# measurement_ch1.net
KiCad netlist of a schematic drawn in Altium Designer
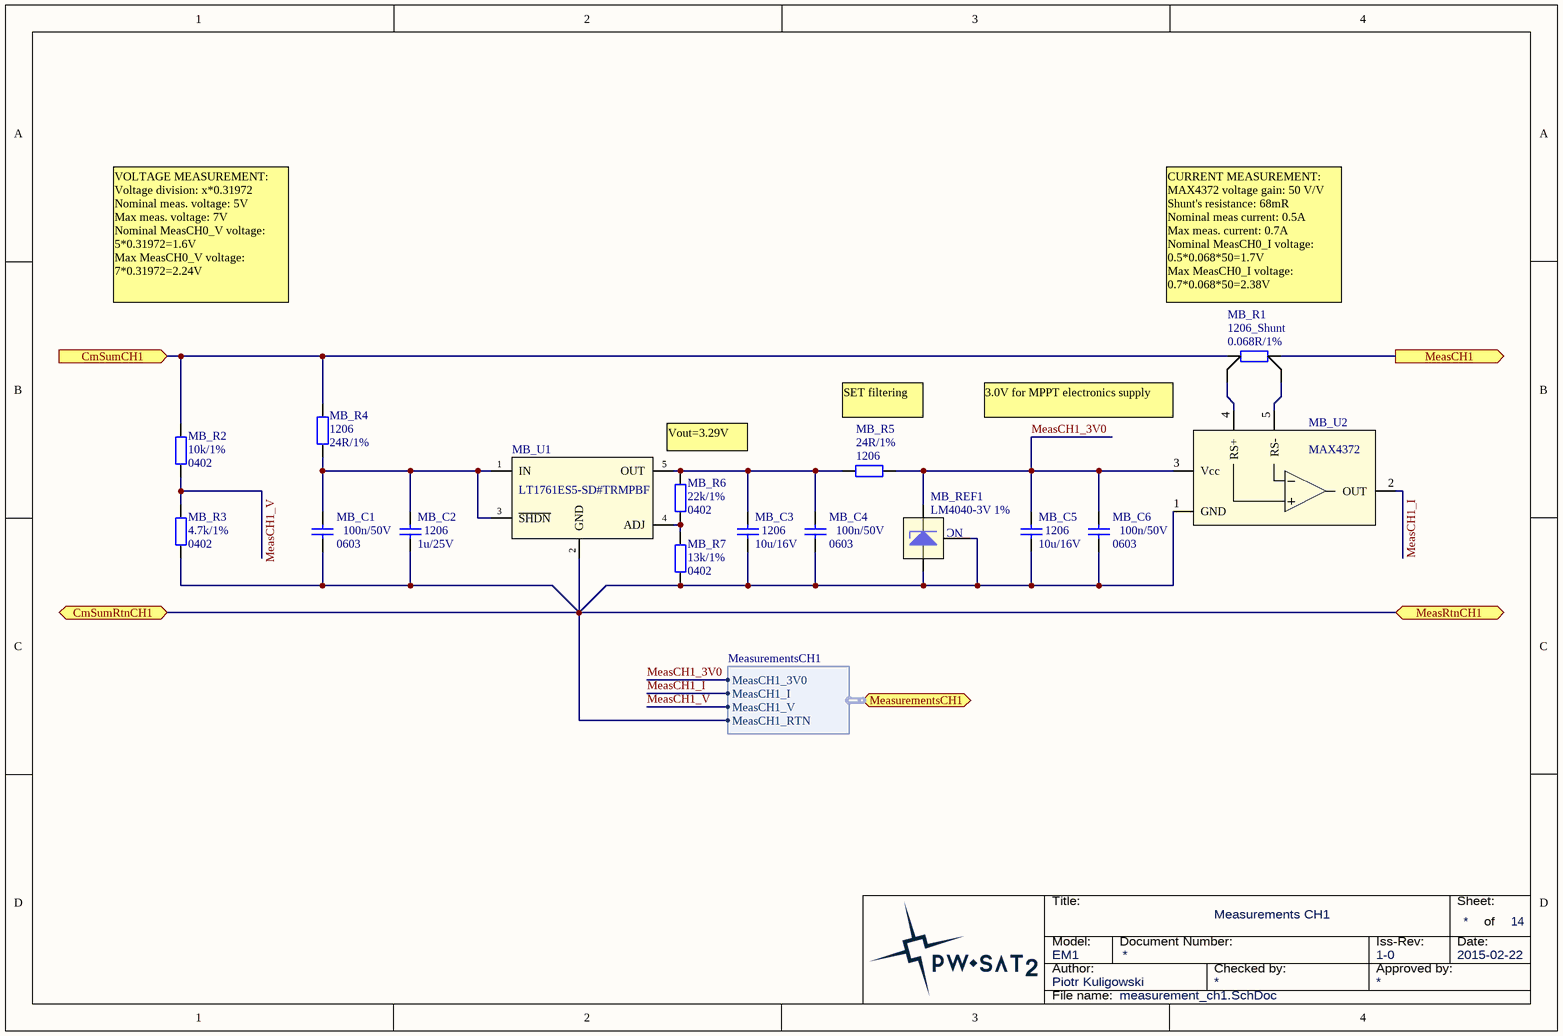
[diagram p0: measurement_ch1.SchDoc]

(export (version "E")
  (design (tool "Eeschema 10.0.6"))
  (components
    (comp (ref "MB_C1")
      (value "100n/50V")
      (footprint "SMD_Capacitor_0603")
      (description "Ceramic Cap Murata Automotive 100n/50V X7R 0603")
      (fields
        (field (name "MANUFACTURER") "Murata")
        (field (name "MANUFACTURERPARTNUMBER") "GCJ188R71H104KA12D")
        (field (name "PACKAGE") "0603")
      )
      (libsource (lib "capacitors") (part "Cer_GCJ188R71H104KA12D"))
    )
    (comp (ref "MB_C2")
      (value "1u/25V")
      (footprint "SMD_Capacitor_1206")
      (description "Ceramic Cap Kemet COTS 1u/25V X7R 1206")
      (fields
        (field (name "MANUFACTURERPARTNUMBER") "C1206T105K3RALTU")
        (field (name "MANUFACTURER") "Kemet")
        (field (name "PACKAGE") "1206")
      )
      (libsource (lib "capacitors") (part "Cer_C1206T105K3RALTU"))
    )
    (comp (ref "MB_C3")
      (value "10u/16V")
      (footprint "SMD_Capacitor_1206")
      (description "Ceramic Cap Kemet COTS 10u/16V X7R 1206")
      (fields
        (field (name "MANUFACTURERPARTNUMBER") "C1206T106K4RACTU")
        (field (name "MANUFACTURER") "Kemet")
        (field (name "PACKGE") "1206")
      )
      (libsource (lib "capacitors") (part "Cer_C1206T106K4RACTU"))
    )
    (comp (ref "MB_C4")
      (value "100n/50V")
      (footprint "SMD_Capacitor_0603")
      (description "Ceramic Cap Murata Automotive 100n/50V X7R 0603")
      (fields
        (field (name "MANUFACTURER") "Murata")
        (field (name "MANUFACTURERPARTNUMBER") "GCJ188R71H104KA12D")
        (field (name "PACKAGE") "0603")
      )
      (libsource (lib "capacitors") (part "Cer_GCJ188R71H104KA12D"))
    )
    (comp (ref "MB_C5")
      (value "10u/16V")
      (footprint "SMD_Capacitor_1206")
      (description "Ceramic Cap Kemet COTS 10u/16V X7R 1206")
      (fields
        (field (name "MANUFACTURERPARTNUMBER") "C1206T106K4RACTU")
        (field (name "MANUFACTURER") "Kemet")
        (field (name "PACKGE") "1206")
      )
      (libsource (lib "capacitors") (part "Cer_C1206T106K4RACTU"))
    )
    (comp (ref "MB_C6")
      (value "100n/50V")
      (footprint "SMD_Capacitor_0603")
      (description "Ceramic Cap Murata Automotive 100n/50V X7R 0603")
      (fields
        (field (name "MANUFACTURER") "Murata")
        (field (name "MANUFACTURERPARTNUMBER") "GCJ188R71H104KA12D")
        (field (name "PACKAGE") "0603")
      )
      (libsource (lib "capacitors") (part "Cer_GCJ188R71H104KA12D"))
    )
    (comp (ref "MB_R1")
      (value "0.068R/1%")
      (footprint "SMD_Resistor-Shunt_1206")
      (description "Panasonic Resistor 68mR 1% 1206 1W")
      (fields
        (field (name "MANUFACTURER") "Panasonic")
        (field (name "MANUFACTURERPARTNUMBER") "ERJ-8BWFR068V")
        (field (name "PACKAGE") "1206_Shunt")
      )
      (libsource (lib "resistors") (part "ERJ-8BWFR068V"))
    )
    (comp (ref "MB_R2")
      (value "10k/1%")
      (footprint "SMD_Resistor_0402")
      (description "10k/1% Vishay CRCW 0402 Resistor. 63mW, 100ppm, 50V.")
      (fields
        (field (name "MANUFACTURER") "Vishay")
        (field (name "MANUFACTURERPARTNUMBER") "CRCW040210K0FKxxxx")
        (field (name "PACKAGE") "0402")
      )
      (libsource (lib "resistors") (part "CRCW040210K0FKxxxx"))
    )
    (comp (ref "MB_R3")
      (value "4.7k/1%")
      (footprint "SMD_Resistor_0402")
      (description "4.7k/1% Vishay CRCW 0402 Resistor. 63mW, 100ppm, 50V.")
      (fields
        (field (name "MANUFACTURERPARTNUMBER") "CRCW04024K70FKxxxx")
        (field (name "MANUFACTURER") "Vishay")
        (field (name "PACKAGE") "0402")
      )
      (libsource (lib "resistors") (part "CRCW04024K70FKxxxx"))
    )
    (comp (ref "MB_R4")
      (value "24R/1%")
      (footprint "SMD_Resistor_1206")
      (description "24R/1% Vishay CRCW 1206 Resistor. 250mW, 100ppm, 200V.")
      (fields
        (field (name "MANUFACTURERPARTNUMBER") "CRCW120624R0FKxxxx")
        (field (name "MANUFACTURER") "Vishay")
        (field (name "PACKAGE") "1206")
      )
      (libsource (lib "resistors") (part "CRCW120624R0FKxxxx"))
    )
    (comp (ref "MB_R5")
      (value "24R/1%")
      (footprint "SMD_Resistor_1206")
      (description "24R/1% Vishay CRCW 1206 Resistor. 250mW, 100ppm, 200V.")
      (fields
        (field (name "MANUFACTURERPARTNUMBER") "CRCW120624R0FKxxxx")
        (field (name "MANUFACTURER") "Vishay")
        (field (name "PACKAGE") "1206")
      )
      (libsource (lib "") (part "CRCW120624R0FKxxxx_1"))
    )
    (comp (ref "MB_R6")
      (value "22k/1%")
      (footprint "SMD_Resistor_0402")
      (description "22k/1% Vishay CRCW 0402 Resistor. 63mW, 100ppm, 50V.")
      (fields
        (field (name "MANUFACTURER") "Vishay")
        (field (name "MANUFACTURERPARTNUMBER") "CRCW040222K0FKxxxx")
        (field (name "PACKAGE") "0402")
      )
      (libsource (lib "resistors") (part "CRCW040222K0FKxxxx"))
    )
    (comp (ref "MB_R7")
      (value "13k/1%")
      (footprint "SMD_Resistor_0402")
      (description "13k/1% Vishay CRCW 0402 Resistor. 63mW, 100ppm, 50V.")
      (fields
        (field (name "MANUFACTURERPARTNUMBER") "CRCW040213K0FKxxxx")
        (field (name "MANUFACTURER") "Vishay")
        (field (name "PACKAGE") "0402")
      )
      (libsource (lib "resistors") (part "CRCW040213K0FKxxxx"))
    )
    (comp (ref "MB_REF1")
      (value "LM4040-3V 1%")
      (footprint "SOT23-3")
      (description "Shunt V-REF, 3V, 1%, SOT23-3")
      (fields
        (field (name "MANUFACTURERPARTNUMBER") "LM4040DIM3-3.0")
        (field (name "MANUFACTURER") "Texas Instruments")
      )
      (libsource (lib "diodes") (part "LM4040DIM3-3.0"))
    )
    (comp (ref "MB_U1")
      (value "LT1761ES5-SD#TRMPBF")
      (footprint "SOT23-5")
      (description "100mA, Regulated, Low Noise, LDO Micropower Regulator in TSOT-23")
      (fields (field (name "MANUFACTURER") "Linear Technology"))
      (libsource (lib "microcircuits") (part "LT1761ES5-SD#TRMPBF"))
    )
    (comp (ref "MB_U2")
      (value "MAX4372")
      (footprint "SOT23-5")
      (description "High-Side Current-Sense Amplifier with Voltage Output")
      (fields (field (name "MANUFACTURER") "Maxim Integrated Products"))
      (libsource (lib "microcircuits") (part "MAX4372"))
    )
  )
  (nets
    (net (code "2") (name "/CmSumCH1") (class "Default")
      (node (ref "MB_R1") (pin "1") (pinfunction "1_1") (pintype "passive"))
      (node (ref "MB_R2") (pin "1") (pinfunction "1_1") (pintype "passive"))
      (node (ref "MB_R4") (pin "1") (pinfunction "1_1") (pintype "passive"))
    )
    (net (code "3") (name "/CmSumRtnCH1") (class "Default")
      (node (ref "MB_C1") (pin "2") (pinfunction "2_2") (pintype "passive"))
      (node (ref "MB_C2") (pin "2") (pinfunction "2_2") (pintype "passive"))
      (node (ref "MB_C3") (pin "2") (pinfunction "2_2") (pintype "passive"))
      (node (ref "MB_C4") (pin "2") (pinfunction "2_2") (pintype "passive"))
      (node (ref "MB_C5") (pin "2") (pinfunction "2_2") (pintype "passive"))
      (node (ref "MB_C6") (pin "2") (pinfunction "2_2") (pintype "passive"))
      (node (ref "MB_R3") (pin "2") (pinfunction "2_2") (pintype "passive"))
      (node (ref "MB_R7") (pin "2") (pinfunction "2_2") (pintype "passive"))
      (node (ref "MB_REF1") (pin "2") (pinfunction "A_2") (pintype "passive"))
      (node (ref "MB_REF1") (pin "3") (pinfunction "NC_3") (pintype "passive"))
      (node (ref "MB_U1") (pin "2") (pinfunction "GND_2") (pintype "passive"))
      (node (ref "MB_U2") (pin "1") (pinfunction "GND_1") (pintype "passive"))
    )
    (net (code "4") (name "/MeasCH1") (class "Default")
      (node (ref "MB_R1") (pin "4") (pinfunction "4_4") (pintype "passive"))
    )
    (net (code "5") (name "/MeasCH1_3V0") (class "Default")
      (node (ref "MB_C5") (pin "1") (pinfunction "1_1") (pintype "passive"))
      (node (ref "MB_C6") (pin "1") (pinfunction "1_1") (pintype "passive"))
      (node (ref "MB_R5") (pin "2") (pinfunction "2_2") (pintype "passive"))
      (node (ref "MB_REF1") (pin "1") (pinfunction "K_1") (pintype "passive"))
      (node (ref "MB_U2") (pin "3") (pinfunction "Vcc_3") (pintype "passive"))
    )
    (net (code "6") (name "/MeasCH1_I") (class "Default")
      (node (ref "MB_U2") (pin "2") (pinfunction "OUT_2") (pintype "passive"))
    )
    (net (code "7") (name "/MeasCH1_V") (class "Default")
      (node (ref "MB_R2") (pin "2") (pinfunction "2_2") (pintype "passive"))
      (node (ref "MB_R3") (pin "1") (pinfunction "1_1") (pintype "passive"))
    )
    (net (code "9") (name "Net-(MB_U1-ADJ)") (class "Default")
      (node (ref "MB_R6") (pin "2") (pinfunction "2_2") (pintype "passive"))
      (node (ref "MB_R7") (pin "1") (pinfunction "1_1") (pintype "passive"))
      (node (ref "MB_U1") (pin "4") (pinfunction "ADJ_4") (pintype "passive"))
    )
    (net (code "10") (name "Net-(MB_U1-IN)") (class "Default")
      (node (ref "MB_C1") (pin "1") (pinfunction "1_1") (pintype "passive"))
      (node (ref "MB_C2") (pin "1") (pinfunction "1_1") (pintype "passive"))
      (node (ref "MB_R4") (pin "2") (pinfunction "2_2") (pintype "passive"))
      (node (ref "MB_U1") (pin "1") (pinfunction "IN_1") (pintype "passive"))
      (node (ref "MB_U1") (pin "3") (pinfunction "~{SHDN}_3") (pintype "passive"))
    )
    (net (code "11") (name "Net-(MB_U1-OUT)") (class "Default")
      (node (ref "MB_C3") (pin "1") (pinfunction "1_1") (pintype "passive"))
      (node (ref "MB_C4") (pin "1") (pinfunction "1_1") (pintype "passive"))
      (node (ref "MB_R5") (pin "1") (pinfunction "1_1") (pintype "passive"))
      (node (ref "MB_R6") (pin "1") (pinfunction "1_1") (pintype "passive"))
      (node (ref "MB_U1") (pin "5") (pinfunction "OUT_5") (pintype "passive"))
    )
    (net (code "12") (name "Net-(MB_U2-RS+)") (class "Default")
      (node (ref "MB_R1") (pin "2") (pinfunction "2_2") (pintype "passive"))
      (node (ref "MB_U2") (pin "4") (pinfunction "RS+_4") (pintype "passive"))
    )
    (net (code "13") (name "Net-(MB_U2-RS-)") (class "Default")
      (node (ref "MB_R1") (pin "3") (pinfunction "3_3") (pintype "passive"))
      (node (ref "MB_U2") (pin "5") (pinfunction "RS-_5") (pintype "passive"))
    )
  )
)
